# EStop.net
KiCad netlist of a schematic drawn in EAGLE
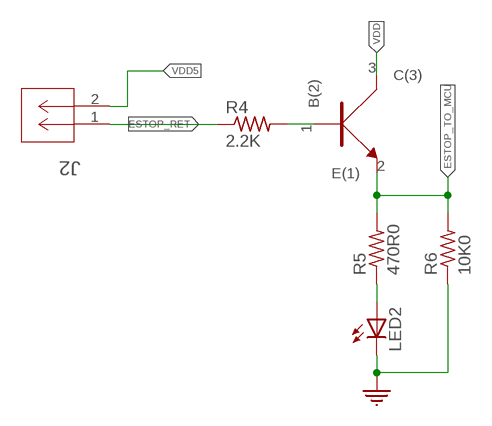
[diagram p0: schematic, sheet 1]

(export (version "E")
  (design (tool "Eeschema 10.0.6"))
  (components
    (comp (ref "J2")
      (value "CONN_530470210_PICOBLADE_X_2")
      (footprint "eagle-import:CON_530470210_MOL")
      (fields
        (field (name "MANUFACTURER_PART_NUMBER") "530470210")
        (field (name "COPYRIGHT") "Copyright (C) 2022 Ultra Librarian. All rights reserved.")
      )
      (libsource (lib "eagle-import") (part "CONN_530470210_PICOBLADE_X_2"))
    )
    (comp (ref "LED2")
      (value "Green")
      (footprint "eagle-import:0805")
      (fields (field (name "PARTNO") "LG R971-KN-1"))
      (libsource (lib "eagle-import") (part "LED_0805_GREEN"))
    )
    (comp (ref "R4")
      (value "2.2K")
      (footprint "eagle-import:0402")
      (libsource (lib "eagle-import") (part "R_0402"))
    )
    (comp (ref "R5")
      (value "470R0")
      (footprint "eagle-import:0402")
      (fields (field (name "PARTNO") "RMCF0402JT470R"))
      (libsource (lib "eagle-import") (part "R_0402_470R0"))
    )
    (comp (ref "R6")
      (value "10K0")
      (footprint "eagle-import:0402")
      (fields (field (name "PARTNO") "RMCF0402JT10K0"))
      (libsource (lib "eagle-import") (part "R_0402_10K0"))
    )
    (comp (ref "U2")
      (value "NPN")
      (footprint "eagle-import:SOT323")
      (fields (field (name "PARTNO") "BC846BW_NPN"))
      (libsource (lib "eagle-import") (part "BC846BW"))
    )
  )
  (nets
    (net (code "1") (name "ESTOP_RET") (class "Default")
      (node (ref "J2") (pin "1") (pinfunction "1_1") (pintype "passive"))
      (node (ref "R4") (pin "P$1") (pinfunction "1_P$1") (pintype "passive"))
    )
    (net (code "2") (name "ESTOP_TO_MCU") (class "Default")
      (node (ref "R5") (pin "P$2") (pinfunction "2_P$2") (pintype "passive"))
      (node (ref "R6") (pin "P$2") (pinfunction "2_P$2") (pintype "passive"))
      (node (ref "U2") (pin "2") (pinfunction "E(1)_2") (pintype "output"))
    )
    (net (code "3") (name "GND") (class "Default")
      (node (ref "LED2") (pin "2") (pinfunction "C_2") (pintype "passive"))
      (node (ref "R6") (pin "P$1") (pinfunction "1_P$1") (pintype "passive"))
    )
    (net (code "4") (name "Net-(LED2-A)") (class "Default")
      (node (ref "LED2") (pin "1") (pinfunction "A_1") (pintype "passive"))
      (node (ref "R5") (pin "P$1") (pinfunction "1_P$1") (pintype "passive"))
    )
    (net (code "5") (name "Net-(R4-2)") (class "Default")
      (node (ref "R4") (pin "P$2") (pinfunction "2_P$2") (pintype "passive"))
      (node (ref "U2") (pin "1") (pinfunction "B(2)_1") (pintype "input"))
    )
    (net (code "6") (name "VDD") (class "Default")
      (node (ref "U2") (pin "3") (pinfunction "C(3)_3") (pintype "input"))
    )
    (net (code "7") (name "VDD5") (class "Default")
      (node (ref "J2") (pin "2") (pinfunction "2_2") (pintype "passive"))
    )
  )
)
